# C-08_SODIMM_-.net
KiCad netlist of a schematic drawn in Altium Designer
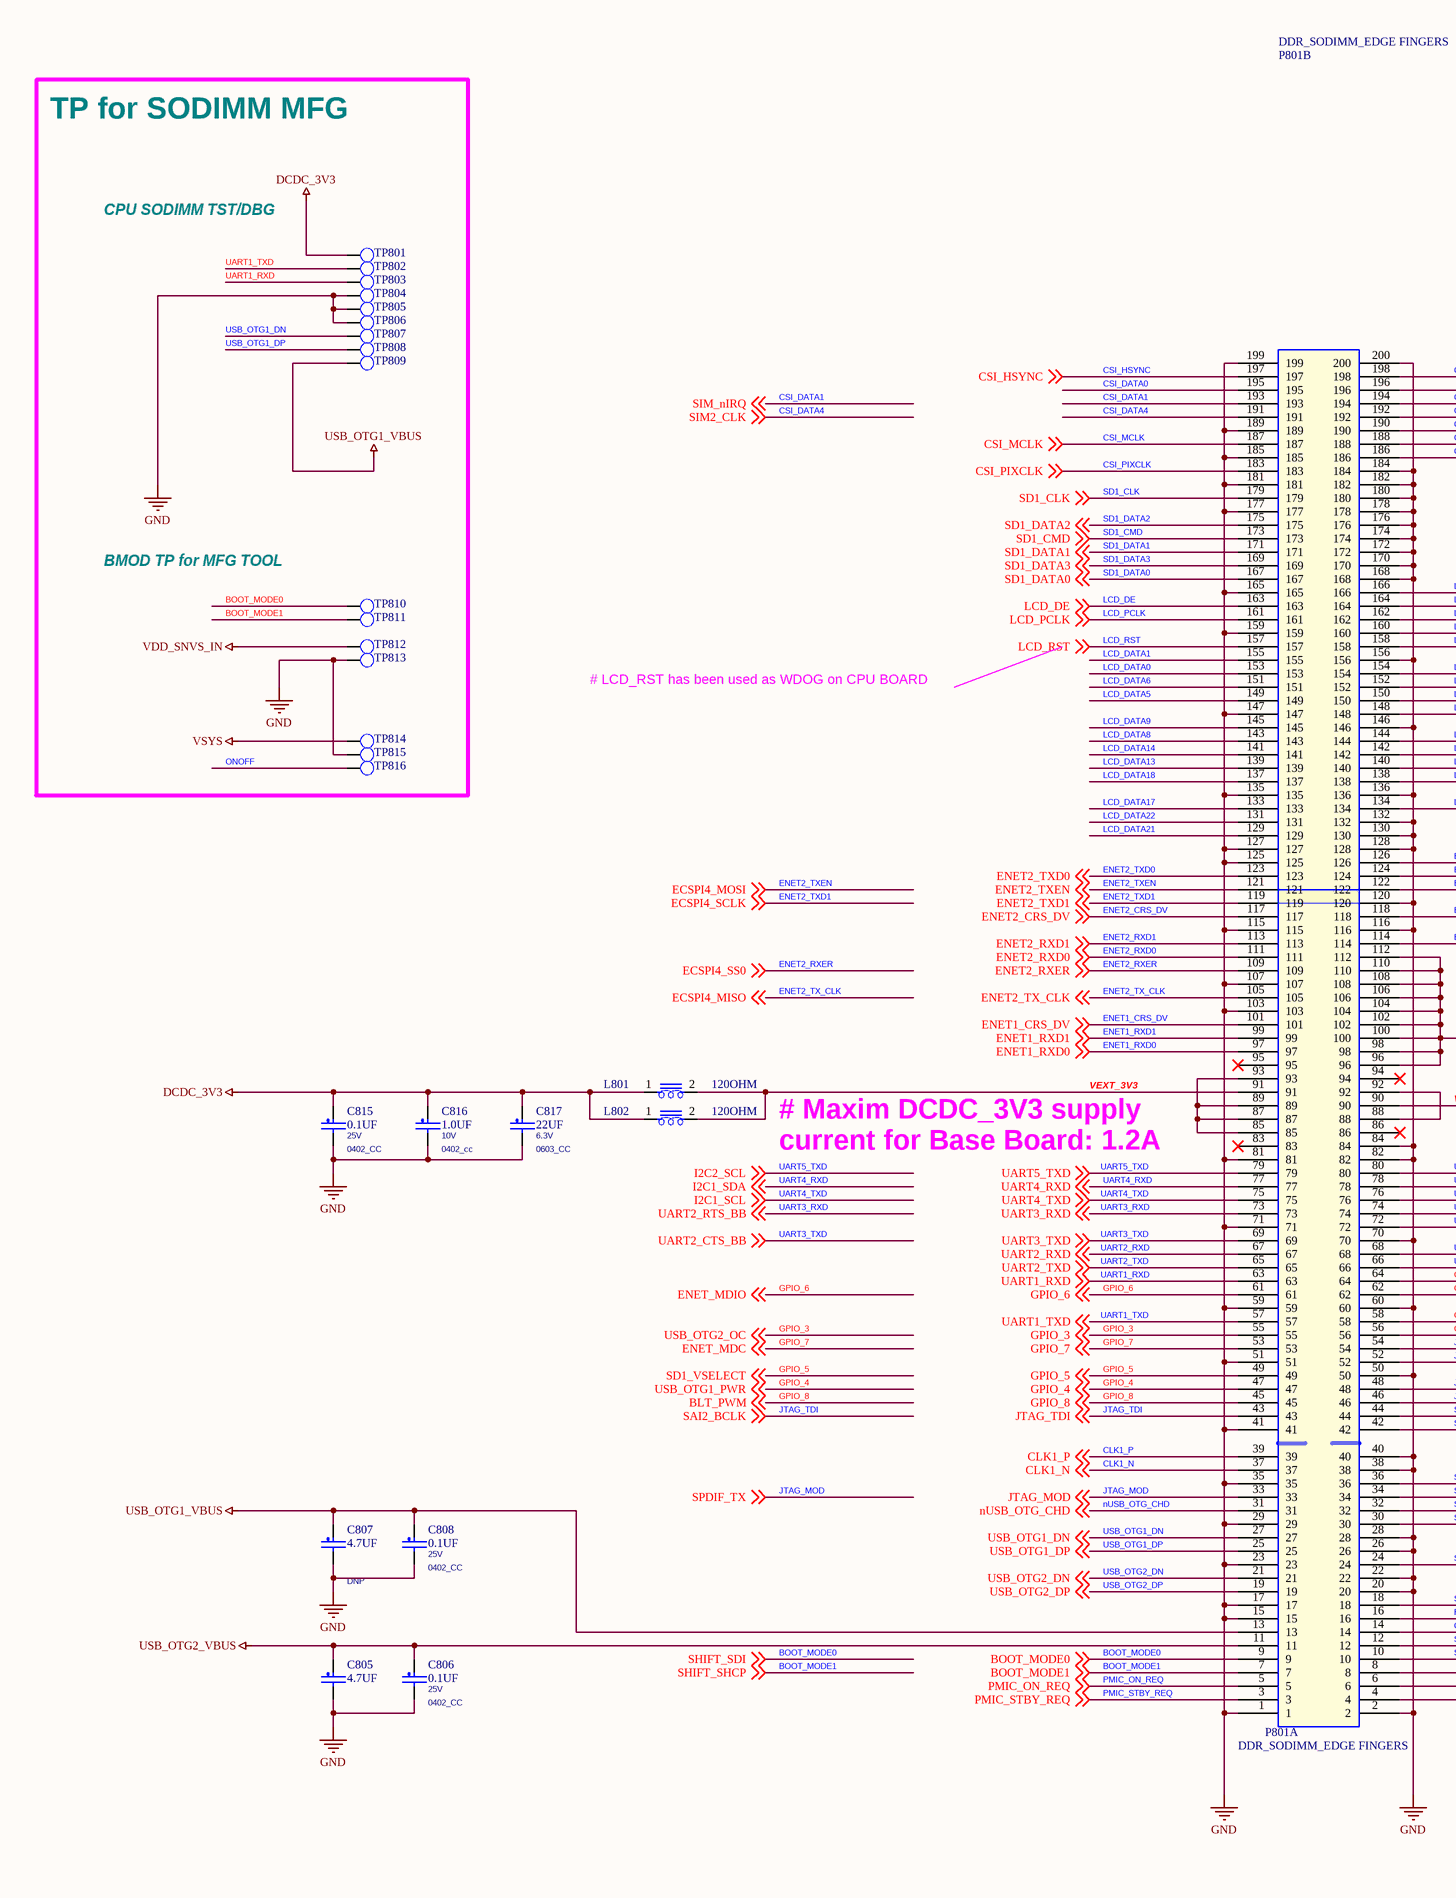
[diagram p0: C-08 SODIMM - 副本.SchDoc, left]
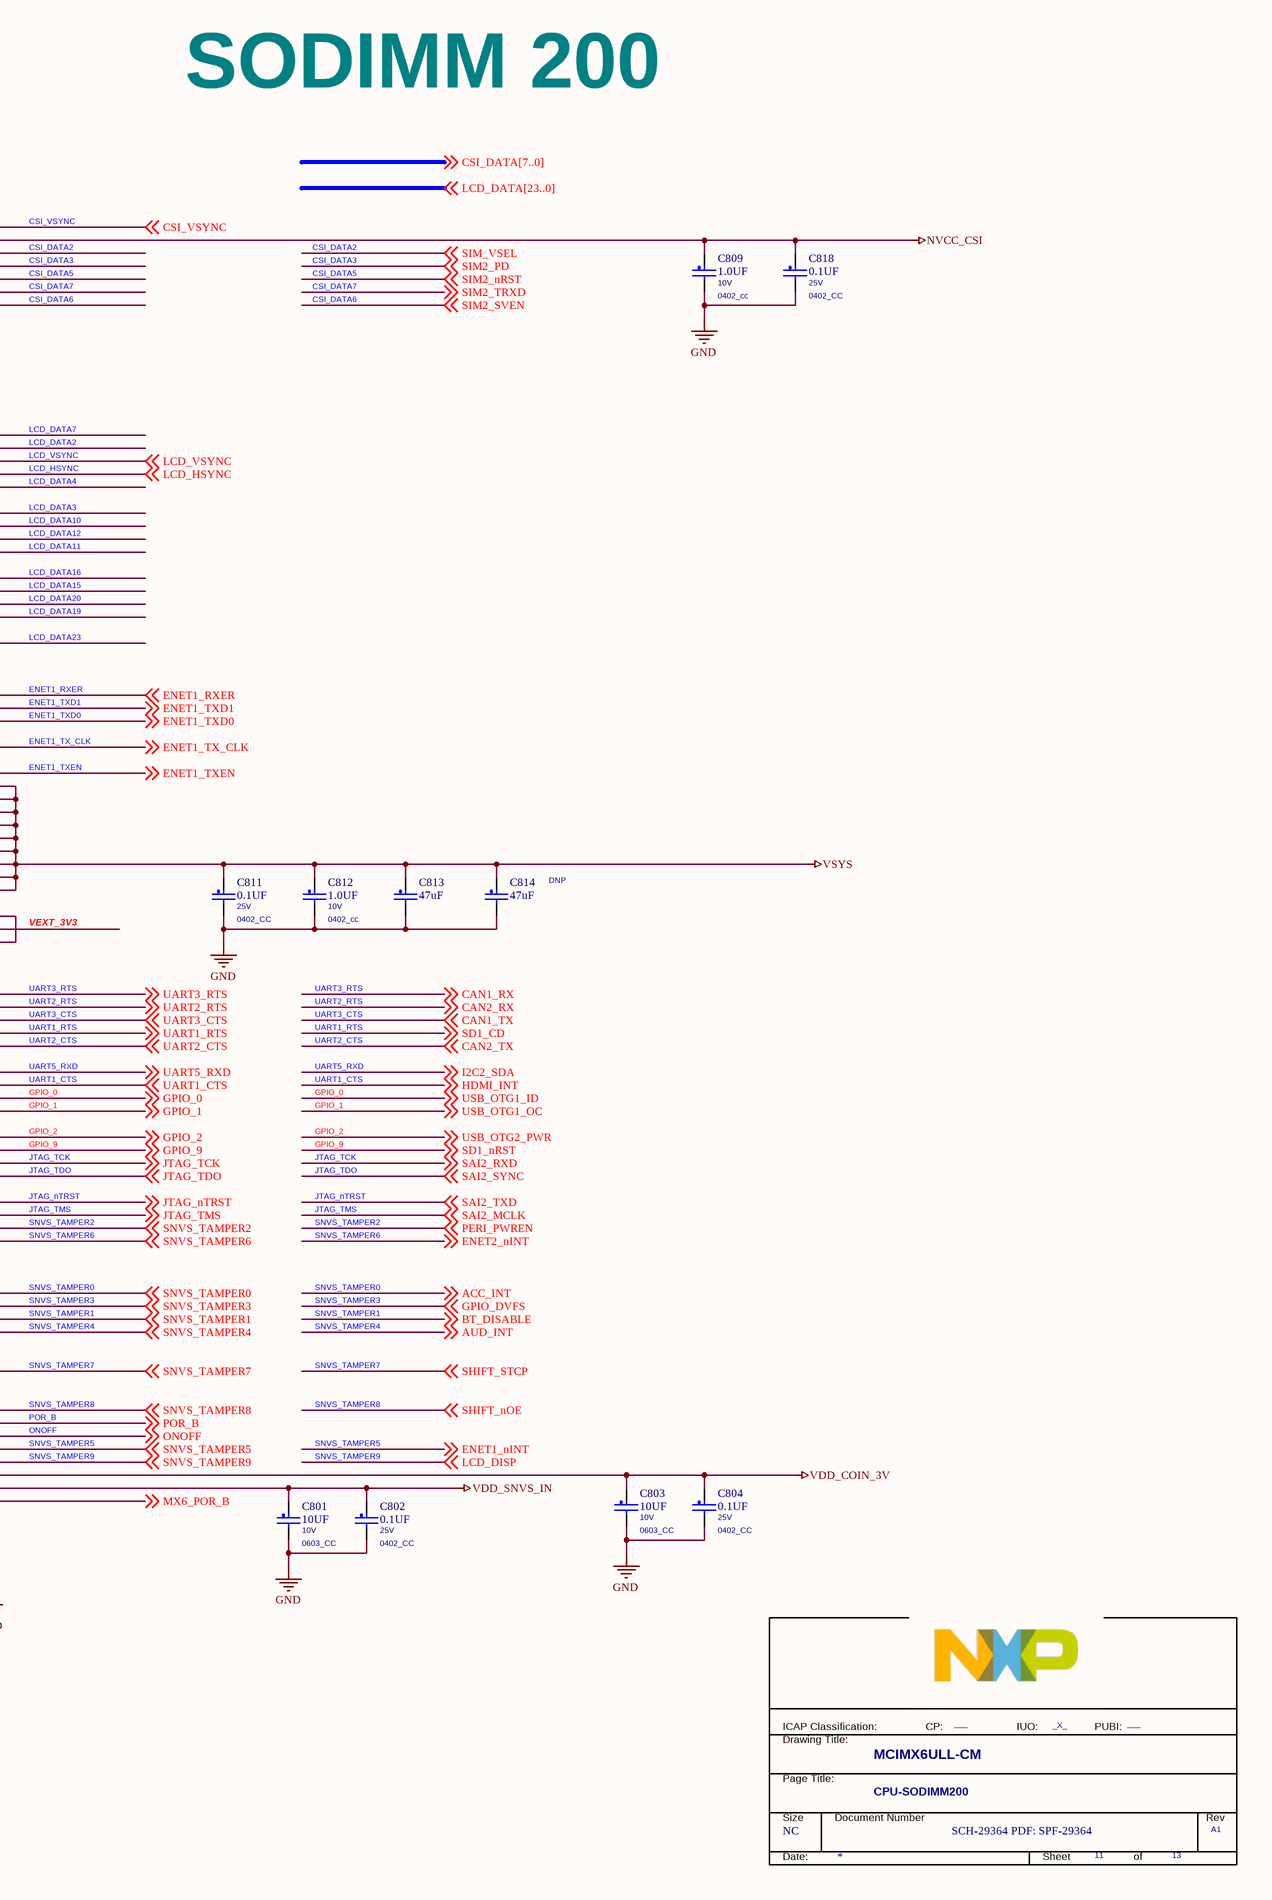
[diagram p1: C-08 SODIMM - 副本.SchDoc, right]

(export (version "E")
  (design (tool "Eeschema 10.0.6"))
  (components
    (comp (ref "*")
      (value "TitleBlock_FS")
      (fields
        (field (name "PAGETITLE") "CPU-SODIMM200")
        (field (name "PAGE COUNT") "13")
        (field (name "PAGE NUMBER") "11")
        (field (name "PAGE SIZE") "NC")
        (field (name "TITLE") "MCIMX6ULL-CM")
        (field (name "REVCODE") "A1")
        (field (name "DOC") "SCH-29364 PDF: SPF-29364")
        (field (name "FCP") "___")
        (field (name "PUBI") "___")
        (field (name "FIUO") "_X_")
      )
      (libsource (lib "*") (part "TitleBlock_FS"))
    )
    (comp (ref "C801")
      (value "10UF")
      (footprint "0603_CC")
      (description "CAP CER 10UF 10V 20% X5R 0603")
      (fields (field (name "VOLTAGE") "10V") (field (name "PCB FOOTPRINT") "0603_CC"))
      (libsource (lib "*") (part "CAP_NP"))
    )
    (comp (ref "C802")
      (value "0.1UF")
      (footprint "0402_CC")
      (description "CAP CER 0.1UF 25V 10% X5R 0402")
      (fields
        (field (name "VOLTAGE") "25V")
        (field (name "TOLERANCE") "10%")
        (field (name "PCB FOOTPRINT") "0402_CC")
      )
      (libsource (lib "*") (part "CAP_NP"))
    )
    (comp (ref "C803")
      (value "10UF")
      (footprint "0603_CC")
      (description "CAP CER 10UF 10V 20% X5R 0603")
      (fields (field (name "VOLTAGE") "10V") (field (name "PCB FOOTPRINT") "0603_CC"))
      (libsource (lib "*") (part "CAP_NP"))
    )
    (comp (ref "C804")
      (value "0.1UF")
      (footprint "0402_CC")
      (description "CAP CER 0.1UF 25V 10% X5R 0402")
      (fields
        (field (name "VOLTAGE") "25V")
        (field (name "TOLERANCE") "10%")
        (field (name "PCB FOOTPRINT") "0402_CC")
      )
      (libsource (lib "*") (part "CAP_NP"))
    )
    (comp (ref "C805")
      (value "4.7UF")
      (footprint "0603_CC")
      (description "CAP CER 4.7uF 16V 10% X5R 0603")
      (fields (field (name "VOLTAGE") "16V") (field (name "TOLERANCE") "10%"))
      (libsource (lib "*") (part "CAP_NP"))
    )
    (comp (ref "C806")
      (value "0.1UF")
      (footprint "0402_CC")
      (description "CAP CER 0.1UF 25V 10% X5R 0402")
      (fields
        (field (name "VOLTAGE") "25V")
        (field (name "TOLERANCE") "10%")
        (field (name "PCB FOOTPRINT") "0402_CC")
      )
      (libsource (lib "*") (part "CAP_NP"))
    )
    (comp (ref "C807")
      (value "4.7UF")
      (footprint "0603_CC")
      (description "CAP CER 4.7uF 16V 10% X5R 0603")
      (fields (field (name "ASSY_OPT") "DNP") (field (name "TOLERANCE") "10%") (field (name "VOLTAGE") "16V"))
      (libsource (lib "*") (part "CAP_NP"))
    )
    (comp (ref "C808")
      (value "0.1UF")
      (footprint "0402_CC")
      (description "CAP CER 0.1UF 25V 10% X5R 0402")
      (fields
        (field (name "VOLTAGE") "25V")
        (field (name "TOLERANCE") "10%")
        (field (name "PCB FOOTPRINT") "0402_CC")
      )
      (libsource (lib "*") (part "CAP_NP"))
    )
    (comp (ref "C809")
      (value "1.0UF")
      (footprint "0402_cc")
      (description "CAP CER 1.0UF 10V 10% X5R 0402")
      (fields (field (name "VOLTAGE") "10V") (field (name "PCB FOOTPRINT") "0402_cc"))
      (libsource (lib "*") (part "CAP_NP"))
    )
    (comp (ref "C811")
      (value "0.1UF")
      (footprint "0402_CC")
      (description "CAP CER 0.1UF 25V 10% X5R 0402")
      (fields
        (field (name "TOLERANCE") "10%")
        (field (name "VOLTAGE") "25V")
        (field (name "PCB FOOTPRINT") "0402_CC")
      )
      (libsource (lib "*") (part "CAP_NP"))
    )
    (comp (ref "C812")
      (value "1.0UF")
      (footprint "0402_cc")
      (description "CAP CER 1.0UF 10V 10% X5R 0402")
      (fields (field (name "VOLTAGE") "10V") (field (name "PCB FOOTPRINT") "0402_cc"))
      (libsource (lib "*") (part "CAP_NP"))
    )
    (comp (ref "C813")
      (value "47uF")
      (footprint "CC0805_OV")
      (description "CAP CER 47uF 10V 20% X5R 0805")
      (fields (field (name "TOLERANCE") "20%") (field (name "VOLTAGE") "10V"))
      (libsource (lib "*") (part "CAP_NP"))
    )
    (comp (ref "C814")
      (value "47uF")
      (footprint "CC0805_OV")
      (description "CAP CER 47uF 10V 20% X5R 0805")
      (fields (field (name "ASSY_OPT") "DNP") (field (name "TOLERANCE") "20%") (field (name "VOLTAGE") "10V"))
      (libsource (lib "*") (part "CAP_NP"))
    )
    (comp (ref "C815")
      (value "0.1UF")
      (footprint "0402_CC")
      (description "CAP CER 0.1UF 25V 10% X5R 0402")
      (fields
        (field (name "TOLERANCE") "10%")
        (field (name "VOLTAGE") "25V")
        (field (name "PCB FOOTPRINT") "0402_CC")
      )
      (libsource (lib "*") (part "CAP_NP"))
    )
    (comp (ref "C816")
      (value "1.0UF")
      (footprint "0402_cc")
      (description "CAP CER 1.0UF 10V 10% X5R 0402")
      (fields (field (name "VOLTAGE") "10V") (field (name "PCB FOOTPRINT") "0402_cc"))
      (libsource (lib "*") (part "CAP_NP"))
    )
    (comp (ref "C817")
      (value "22UF")
      (footprint "0603_CC")
      (description "CAP CER 22UF 6.3V 20% X5R 0603")
      (fields
        (field (name "VOLTAGE RATING") "6.3V")
        (field (name "TOLERANCE") "20%")
        (field (name "VOLTAGE") "6.3V")
        (field (name "PCB FOOTPRINT") "0603_CC")
      )
      (libsource (lib "*") (part "CAP_NP"))
    )
    (comp (ref "C818")
      (value "0.1UF")
      (footprint "0402_CC")
      (description "CAP CER 0.1UF 25V 10% X5R 0402")
      (fields
        (field (name "TOLERANCE") "10%")
        (field (name "VOLTAGE") "25V")
        (field (name "PCB FOOTPRINT") "0402_CC")
      )
      (libsource (lib "*") (part "CAP_NP"))
    )
    (comp (ref "L801")
      (value "120OHM")
      (footprint "0603_CC")
      (description "IND FER BEAD 120OHM@100MHZ 2A 25% 0603")
      (fields (field (name "TOLERANCE") "25%"))
      (libsource (lib "*") (part "BEAD_0"))
    )
    (comp (ref "L802")
      (value "120OHM")
      (footprint "0603_CC")
      (description "IND FER BEAD 120OHM@100MHZ 2A 25% 0603")
      (fields (field (name "TOLERANCE") "25%"))
      (libsource (lib "*") (part "BEAD_0"))
    )
    (comp (ref "P801")
      (value "DDR_SODIMM_EDGE FINGERS")
      (footprint "SODIMM_67589")
      (description "200 PIN SODIMM EDGE FINGERS -- AU FOOTPRINT ONLY, NO PART TO ORDER")
      (libsource (lib "*") (part "CONN_EDGE_200P"))
    )
    (comp (ref "TP801")
      (value "TP_35MIL")
      (footprint "testpoint_35mil")
      (description "TEST POINT PAD .035 SMT, no part to order")
      (libsource (lib "*") (part "T POINT R"))
    )
    (comp (ref "TP802")
      (value "TP_35MIL")
      (footprint "testpoint_35mil")
      (description "TEST POINT PAD .035 SMT, no part to order")
      (libsource (lib "*") (part "T POINT R"))
    )
    (comp (ref "TP803")
      (value "TP_35MIL")
      (footprint "testpoint_35mil")
      (description "TEST POINT PAD .035 SMT, no part to order")
      (libsource (lib "*") (part "T POINT R"))
    )
    (comp (ref "TP804")
      (value "TP_35MIL")
      (footprint "testpoint_35mil")
      (description "TEST POINT PAD .035 SMT, no part to order")
      (libsource (lib "*") (part "T POINT R"))
    )
    (comp (ref "TP805")
      (value "TP_35MIL")
      (footprint "testpoint_35mil")
      (description "TEST POINT PAD .035 SMT, no part to order")
      (libsource (lib "*") (part "T POINT R"))
    )
    (comp (ref "TP806")
      (value "TP_35MIL")
      (footprint "testpoint_35mil")
      (description "TEST POINT PAD .035 SMT, no part to order")
      (libsource (lib "*") (part "T POINT R"))
    )
    (comp (ref "TP807")
      (value "TP_35MIL")
      (footprint "testpoint_35mil")
      (description "TEST POINT PAD .035 SMT, no part to order")
      (libsource (lib "*") (part "T POINT R"))
    )
    (comp (ref "TP808")
      (value "TP_35MIL")
      (footprint "testpoint_35mil")
      (description "TEST POINT PAD .035 SMT, no part to order")
      (libsource (lib "*") (part "T POINT R"))
    )
    (comp (ref "TP809")
      (value "TP_35MIL")
      (footprint "testpoint_35mil")
      (description "TEST POINT PAD .035 SMT, no part to order")
      (libsource (lib "*") (part "T POINT R"))
    )
    (comp (ref "TP810")
      (value "TP_35MIL")
      (footprint "testpoint_35mil")
      (description "TEST POINT PAD .035 SMT, no part to order")
      (libsource (lib "*") (part "T POINT R"))
    )
    (comp (ref "TP811")
      (value "TP_35MIL")
      (footprint "testpoint_35mil")
      (description "TEST POINT PAD .035 SMT, no part to order")
      (libsource (lib "*") (part "T POINT R"))
    )
    (comp (ref "TP812")
      (value "TP_35MIL")
      (footprint "testpoint_35mil")
      (description "TEST POINT PAD .035 SMT, no part to order")
      (libsource (lib "*") (part "T POINT R"))
    )
    (comp (ref "TP813")
      (value "TP_35MIL")
      (footprint "testpoint_35mil")
      (description "TEST POINT PAD .035 SMT, no part to order")
      (libsource (lib "*") (part "T POINT R"))
    )
    (comp (ref "TP814")
      (value "TP_35MIL")
      (footprint "testpoint_35mil")
      (description "TEST POINT PAD .035 SMT, no part to order")
      (libsource (lib "*") (part "T POINT R"))
    )
    (comp (ref "TP815")
      (value "TP_35MIL")
      (footprint "testpoint_35mil")
      (description "TEST POINT PAD .035 SMT, no part to order")
      (libsource (lib "*") (part "T POINT R"))
    )
    (comp (ref "TP816")
      (value "TP_35MIL")
      (footprint "testpoint_35mil")
      (description "TEST POINT PAD .035 SMT, no part to order")
      (libsource (lib "*") (part "T POINT R"))
    )
  )
  (nets
    (net (code "1") (name "/VEXT_3V3") (class "Default")
      (node (ref "L801") (pin "2") (pinfunction "2_2") (pintype "passive"))
      (node (ref "L802") (pin "2") (pinfunction "2_2") (pintype "passive"))
      (node (ref "P801") (pin "90") (pinfunction "90_90") (pintype "passive"))
      (node (ref "P801") (pin "91") (pinfunction "91_91") (pintype "passive"))
    )
    (net (code "2") (name "ACC_INT") (class "Default")
      (node (ref "P801") (pin "36") (pinfunction "36_36") (pintype "passive"))
    )
    (net (code "3") (name "AUD_INT") (class "Default")
      (node (ref "P801") (pin "30") (pinfunction "30_30") (pintype "passive"))
    )
    (net (code "4") (name "BLT_PWM") (class "Default")
      (node (ref "P801") (pin "45") (pinfunction "45_45") (pintype "passive"))
    )
    (net (code "5") (name "BOOT_MODE0") (class "Default")
      (node (ref "P801") (pin "9") (pinfunction "9_9") (pintype "passive"))
      (node (ref "TP810") (pin "1") (pinfunction "TP_1") (pintype "passive"))
    )
    (net (code "6") (name "BOOT_MODE1") (class "Default")
      (node (ref "P801") (pin "7") (pinfunction "7_7") (pintype "passive"))
      (node (ref "TP811") (pin "1") (pinfunction "TP_1") (pintype "passive"))
    )
    (net (code "7") (name "BT_DISABLE") (class "Default")
      (node (ref "P801") (pin "32") (pinfunction "32_32") (pintype "passive"))
    )
    (net (code "8") (name "CAN1_RX") (class "Default")
      (node (ref "P801") (pin "80") (pinfunction "80_80") (pintype "passive"))
    )
    (net (code "9") (name "CAN1_TX") (class "Default")
      (node (ref "P801") (pin "76") (pinfunction "76_76") (pintype "passive"))
    )
    (net (code "10") (name "CAN2_RX") (class "Default")
      (node (ref "P801") (pin "78") (pinfunction "78_78") (pintype "passive"))
    )
    (net (code "11") (name "CAN2_TX") (class "Default")
      (node (ref "P801") (pin "72") (pinfunction "72_72") (pintype "passive"))
    )
    (net (code "12") (name "CLK1_N") (class "Default")
      (node (ref "P801") (pin "37") (pinfunction "37_37") (pintype "passive"))
    )
    (net (code "13") (name "CLK1_P") (class "Default")
      (node (ref "P801") (pin "39") (pinfunction "39_39") (pintype "passive"))
    )
    (net (code "14") (name "CSI_DATA0") (class "Default")
      (node (ref "P801") (pin "195") (pinfunction "195_195") (pintype "passive"))
    )
    (net (code "16") (name "CSI_HSYNC") (class "Default")
      (node (ref "P801") (pin "197") (pinfunction "197_197") (pintype "passive"))
    )
    (net (code "17") (name "CSI_MCLK") (class "Default")
      (node (ref "P801") (pin "187") (pinfunction "187_187") (pintype "passive"))
    )
    (net (code "18") (name "CSI_PIXCLK") (class "Default")
      (node (ref "P801") (pin "183") (pinfunction "183_183") (pintype "passive"))
    )
    (net (code "19") (name "CSI_VSYNC") (class "Default")
      (node (ref "P801") (pin "198") (pinfunction "198_198") (pintype "passive"))
    )
    (net (code "20") (name "DCDC_3V3") (class "Default")
      (node (ref "C815") (pin "1") (pinfunction "1_1") (pintype "passive"))
      (node (ref "C816") (pin "1") (pinfunction "1_1") (pintype "passive"))
      (node (ref "C817") (pin "1") (pinfunction "1_1") (pintype "passive"))
      (node (ref "L801") (pin "1") (pinfunction "1_1") (pintype "passive"))
      (node (ref "L802") (pin "1") (pinfunction "1_1") (pintype "passive"))
      (node (ref "TP801") (pin "1") (pinfunction "TP_1") (pintype "passive"))
    )
    (net (code "21") (name "ECSPI4_MISO") (class "Default")
      (node (ref "P801") (pin "105") (pinfunction "105_105") (pintype "passive"))
    )
    (net (code "22") (name "ECSPI4_MOSI") (class "Default")
      (node (ref "P801") (pin "121") (pinfunction "121_121") (pintype "passive"))
    )
    (net (code "23") (name "ECSPI4_SCLK") (class "Default")
      (node (ref "P801") (pin "119") (pinfunction "119_119") (pintype "passive"))
    )
    (net (code "24") (name "ECSPI4_SS0") (class "Default")
      (node (ref "P801") (pin "109") (pinfunction "109_109") (pintype "passive"))
    )
    (net (code "25") (name "ENET1_CRS_DV") (class "Default")
      (node (ref "P801") (pin "101") (pinfunction "101_101") (pintype "passive"))
    )
    (net (code "26") (name "ENET1_RXD0") (class "Default")
      (node (ref "P801") (pin "97") (pinfunction "97_97") (pintype "passive"))
    )
    (net (code "27") (name "ENET1_RXD1") (class "Default")
      (node (ref "P801") (pin "99") (pinfunction "99_99") (pintype "passive"))
    )
    (net (code "28") (name "ENET1_RXER") (class "Default")
      (node (ref "P801") (pin "126") (pinfunction "126_126") (pintype "passive"))
    )
    (net (code "29") (name "ENET1_TXD0") (class "Default")
      (node (ref "P801") (pin "122") (pinfunction "122_122") (pintype "passive"))
    )
    (net (code "30") (name "ENET1_TXD1") (class "Default")
      (node (ref "P801") (pin "124") (pinfunction "124_124") (pintype "passive"))
    )
    (net (code "31") (name "ENET1_TXEN") (class "Default")
      (node (ref "P801") (pin "114") (pinfunction "114_114") (pintype "passive"))
    )
    (net (code "32") (name "ENET1_TX_CLK") (class "Default")
      (node (ref "P801") (pin "118") (pinfunction "118_118") (pintype "passive"))
    )
    (net (code "33") (name "ENET1_nINT") (class "Default")
      (node (ref "P801") (pin "12") (pinfunction "12_12") (pintype "passive"))
    )
    (net (code "34") (name "ENET2_CRS_DV") (class "Default")
      (node (ref "P801") (pin "117") (pinfunction "117_117") (pintype "passive"))
    )
    (net (code "35") (name "ENET2_RXD0") (class "Default")
      (node (ref "P801") (pin "111") (pinfunction "111_111") (pintype "passive"))
    )
    (net (code "36") (name "ENET2_RXD1") (class "Default")
      (node (ref "P801") (pin "113") (pinfunction "113_113") (pintype "passive"))
    )
    (net (code "37") (name "ENET2_TXD0") (class "Default")
      (node (ref "P801") (pin "123") (pinfunction "123_123") (pintype "passive"))
    )
    (net (code "38") (name "ENET2_nINT") (class "Default")
      (node (ref "P801") (pin "42") (pinfunction "42_42") (pintype "passive"))
    )
    (net (code "39") (name "ENET_MDC") (class "Default")
      (node (ref "P801") (pin "53") (pinfunction "53_53") (pintype "passive"))
    )
    (net (code "40") (name "ENET_MDIO") (class "Default")
      (node (ref "P801") (pin "61") (pinfunction "61_61") (pintype "passive"))
    )
    (net (code "41") (name "GND") (class "Default")
      (node (ref "C801") (pin "2") (pinfunction "2_2") (pintype "passive"))
      (node (ref "C802") (pin "2") (pinfunction "2_2") (pintype "passive"))
      (node (ref "C803") (pin "2") (pinfunction "2_2") (pintype "passive"))
      (node (ref "C804") (pin "2") (pinfunction "2_2") (pintype "passive"))
      (node (ref "C805") (pin "2") (pinfunction "2_2") (pintype "passive"))
      (node (ref "C806") (pin "2") (pinfunction "2_2") (pintype "passive"))
      (node (ref "C807") (pin "2") (pinfunction "2_2") (pintype "passive"))
      (node (ref "C808") (pin "2") (pinfunction "2_2") (pintype "passive"))
      (node (ref "C809") (pin "2") (pinfunction "2_2") (pintype "passive"))
      (node (ref "C811") (pin "2") (pinfunction "2_2") (pintype "passive"))
      (node (ref "C812") (pin "2") (pinfunction "2_2") (pintype "passive"))
      (node (ref "C813") (pin "2") (pinfunction "2_2") (pintype "passive"))
      (node (ref "C814") (pin "2") (pinfunction "2_2") (pintype "passive"))
      (node (ref "C815") (pin "2") (pinfunction "2_2") (pintype "passive"))
      (node (ref "C816") (pin "2") (pinfunction "2_2") (pintype "passive"))
      (node (ref "C817") (pin "2") (pinfunction "2_2") (pintype "passive"))
      (node (ref "C818") (pin "2") (pinfunction "2_2") (pintype "passive"))
      (node (ref "P801") (pin "1") (pinfunction "1_1") (pintype "passive"))
      (node (ref "P801") (pin "103") (pinfunction "103_103") (pintype "passive"))
      (node (ref "P801") (pin "107") (pinfunction "107_107") (pintype "passive"))
      (node (ref "P801") (pin "115") (pinfunction "115_115") (pintype "passive"))
      (node (ref "P801") (pin "116") (pinfunction "116_116") (pintype "passive"))
      (node (ref "P801") (pin "120") (pinfunction "120_120") (pintype "passive"))
      (node (ref "P801") (pin "125") (pinfunction "125_125") (pintype "passive"))
      (node (ref "P801") (pin "127") (pinfunction "127_127") (pintype "passive"))
      (node (ref "P801") (pin "128") (pinfunction "128_128") (pintype "passive"))
      (node (ref "P801") (pin "130") (pinfunction "130_130") (pintype "passive"))
      (node (ref "P801") (pin "132") (pinfunction "132_132") (pintype "passive"))
      (node (ref "P801") (pin "135") (pinfunction "135_135") (pintype "passive"))
      (node (ref "P801") (pin "136") (pinfunction "136_136") (pintype "passive"))
      (node (ref "P801") (pin "146") (pinfunction "146_146") (pintype "passive"))
      (node (ref "P801") (pin "147") (pinfunction "147_147") (pintype "passive"))
      (node (ref "P801") (pin "15") (pinfunction "15_15") (pintype "passive"))
      (node (ref "P801") (pin "156") (pinfunction "156_156") (pintype "passive"))
      (node (ref "P801") (pin "159") (pinfunction "159_159") (pintype "passive"))
      (node (ref "P801") (pin "165") (pinfunction "165_165") (pintype "passive"))
      (node (ref "P801") (pin "168") (pinfunction "168_168") (pintype "passive"))
      (node (ref "P801") (pin "17") (pinfunction "17_17") (pintype "passive"))
      (node (ref "P801") (pin "170") (pinfunction "170_170") (pintype "passive"))
      (node (ref "P801") (pin "172") (pinfunction "172_172") (pintype "passive"))
      (node (ref "P801") (pin "174") (pinfunction "174_174") (pintype "passive"))
      (node (ref "P801") (pin "176") (pinfunction "176_176") (pintype "passive"))
      (node (ref "P801") (pin "177") (pinfunction "177_177") (pintype "passive"))
      (node (ref "P801") (pin "178") (pinfunction "178_178") (pintype "passive"))
      (node (ref "P801") (pin "180") (pinfunction "180_180") (pintype "passive"))
      (node (ref "P801") (pin "181") (pinfunction "181_181") (pintype "passive"))
      (node (ref "P801") (pin "182") (pinfunction "182_182") (pintype "passive"))
      (node (ref "P801") (pin "184") (pinfunction "184_184") (pintype "passive"))
      (node (ref "P801") (pin "185") (pinfunction "185_185") (pintype "passive"))
      (node (ref "P801") (pin "189") (pinfunction "189_189") (pintype "passive"))
      (node (ref "P801") (pin "199") (pinfunction "199_199") (pintype "passive"))
      (node (ref "P801") (pin "2") (pinfunction "2_2") (pintype "passive"))
      (node (ref "P801") (pin "20") (pinfunction "20_20") (pintype "passive"))
      (node (ref "P801") (pin "200") (pinfunction "200_200") (pintype "passive"))
      (node (ref "P801") (pin "22") (pinfunction "22_22") (pintype "passive"))
      (node (ref "P801") (pin "23") (pinfunction "23_23") (pintype "passive"))
      (node (ref "P801") (pin "26") (pinfunction "26_26") (pintype "passive"))
      (node (ref "P801") (pin "28") (pinfunction "28_28") (pintype "passive"))
      (node (ref "P801") (pin "29") (pinfunction "29_29") (pintype "passive"))
      (node (ref "P801") (pin "35") (pinfunction "35_35") (pintype "passive"))
      (node (ref "P801") (pin "38") (pinfunction "38_38") (pintype "passive"))
      (node (ref "P801") (pin "40") (pinfunction "40_40") (pintype "passive"))
      (node (ref "P801") (pin "41") (pinfunction "41_41") (pintype "passive"))
      (node (ref "P801") (pin "50") (pinfunction "50_50") (pintype "passive"))
      (node (ref "P801") (pin "51") (pinfunction "51_51") (pintype "passive"))
      (node (ref "P801") (pin "59") (pinfunction "59_59") (pintype "passive"))
      (node (ref "P801") (pin "60") (pinfunction "60_60") (pintype "passive"))
      (node (ref "P801") (pin "70") (pinfunction "70_70") (pintype "passive"))
      (node (ref "P801") (pin "71") (pinfunction "71_71") (pintype "passive"))
      (node (ref "P801") (pin "81") (pinfunction "81_81") (pintype "passive"))
      (node (ref "P801") (pin "82") (pinfunction "82_82") (pintype "passive"))
      (node (ref "P801") (pin "84") (pinfunction "84_84") (pintype "passive"))
      (node (ref "TP804") (pin "1") (pinfunction "TP_1") (pintype "passive"))
      (node (ref "TP805") (pin "1") (pinfunction "TP_1") (pintype "passive"))
      (node (ref "TP806") (pin "1") (pinfunction "TP_1") (pintype "passive"))
      (node (ref "TP813") (pin "1") (pinfunction "TP_1") (pintype "passive"))
      (node (ref "TP815") (pin "1") (pinfunction "TP_1") (pintype "passive"))
    )
    (net (code "42") (name "GPIO_0") (class "Default")
      (node (ref "P801") (pin "64") (pinfunction "64_64") (pintype "passive"))
    )
    (net (code "43") (name "GPIO_1") (class "Default")
      (node (ref "P801") (pin "62") (pinfunction "62_62") (pintype "passive"))
    )
    (net (code "44") (name "GPIO_2") (class "Default")
      (node (ref "P801") (pin "58") (pinfunction "58_58") (pintype "passive"))
    )
    (net (code "45") (name "GPIO_3") (class "Default")
      (node (ref "P801") (pin "55") (pinfunction "55_55") (pintype "passive"))
    )
    (net (code "46") (name "GPIO_4") (class "Default")
      (node (ref "P801") (pin "47") (pinfunction "47_47") (pintype "passive"))
    )
    (net (code "47") (name "GPIO_5") (class "Default")
      (node (ref "P801") (pin "49") (pinfunction "49_49") (pintype "passive"))
    )
    (net (code "48") (name "GPIO_9") (class "Default")
      (node (ref "P801") (pin "56") (pinfunction "56_56") (pintype "passive"))
    )
    (net (code "49") (name "GPIO_DVFS") (class "Default")
      (node (ref "P801") (pin "34") (pinfunction "34_34") (pintype "passive"))
    )
    (net (code "50") (name "HDMI_INT") (class "Default")
      (node (ref "P801") (pin "66") (pinfunction "66_66") (pintype "passive"))
    )
    (net (code "51") (name "I2C1_SCL") (class "Default")
      (node (ref "P801") (pin "75") (pinfunction "75_75") (pintype "passive"))
    )
    (net (code "52") (name "I2C1_SDA") (class "Default")
      (node (ref "P801") (pin "77") (pinfunction "77_77") (pintype "passive"))
    )
    (net (code "53") (name "I2C2_SCL") (class "Default")
      (node (ref "P801") (pin "79") (pinfunction "79_79") (pintype "passive"))
    )
    (net (code "54") (name "I2C2_SDA") (class "Default")
      (node (ref "P801") (pin "68") (pinfunction "68_68") (pintype "passive"))
    )
    (net (code "55") (name "JTAG_MOD") (class "Default")
      (node (ref "P801") (pin "33") (pinfunction "33_33") (pintype "passive"))
    )
    (net (code "56") (name "JTAG_TCK") (class "Default")
      (node (ref "P801") (pin "54") (pinfunction "54_54") (pintype "passive"))
    )
    (net (code "57") (name "JTAG_TDI") (class "Default")
      (node (ref "P801") (pin "43") (pinfunction "43_43") (pintype "passive"))
    )
    (net (code "58") (name "JTAG_TDO") (class "Default")
      (node (ref "P801") (pin "52") (pinfunction "52_52") (pintype "passive"))
    )
    (net (code "59") (name "JTAG_TMS") (class "Default")
      (node (ref "P801") (pin "46") (pinfunction "46_46") (pintype "passive"))
    )
    (net (code "60") (name "JTAG_nTRST") (class "Default")
      (node (ref "P801") (pin "48") (pinfunction "48_48") (pintype "passive"))
    )
    (net (code "61") (name "LCD_DATA0") (class "Default")
      (node (ref "P801") (pin "153") (pinfunction "153_153") (pintype "passive"))
    )
    (net (code "62") (name "LCD_DATA1") (class "Default")
      (node (ref "P801") (pin "155") (pinfunction "155_155") (pintype "passive"))
    )
    (net (code "63") (name "LCD_DATA2") (class "Default")
      (node (ref "P801") (pin "164") (pinfunction "164_164") (pintype "passive"))
    )
    (net (code "64") (name "LCD_DATA3") (class "Default")
      (node (ref "P801") (pin "154") (pinfunction "154_154") (pintype "passive"))
    )
    (net (code "65") (name "LCD_DATA4") (class "Default")
      (node (ref "P801") (pin "158") (pinfunction "158_158") (pintype "passive"))
    )
    (net (code "66") (name "LCD_DATA5") (class "Default")
      (node (ref "P801") (pin "149") (pinfunction "149_149") (pintype "passive"))
    )
    (net (code "67") (name "LCD_DATA6") (class "Default")
      (node (ref "P801") (pin "151") (pinfunction "151_151") (pintype "passive"))
    )
    (net (code "68") (name "LCD_DATA7") (class "Default")
      (node (ref "P801") (pin "166") (pinfunction "166_166") (pintype "passive"))
    )
    (net (code "69") (name "LCD_DATA8") (class "Default")
      (node (ref "P801") (pin "143") (pinfunction "143_143") (pintype "passive"))
    )
    (net (code "70") (name "LCD_DATA9") (class "Default")
      (node (ref "P801") (pin "145") (pinfunction "145_145") (pintype "passive"))
    )
    (net (code "71") (name "LCD_DATA10") (class "Default")
      (node (ref "P801") (pin "152") (pinfunction "152_152") (pintype "passive"))
    )
    (net (code "72") (name "LCD_DATA11") (class "Default")
      (node (ref "P801") (pin "148") (pinfunction "148_148") (pintype "passive"))
    )
    (net (code "73") (name "LCD_DATA12") (class "Default")
      (node (ref "P801") (pin "150") (pinfunction "150_150") (pintype "passive"))
    )
    (net (code "74") (name "LCD_DATA13") (class "Default")
      (node (ref "P801") (pin "139") (pinfunction "139_139") (pintype "passive"))
    )
    (net (code "75") (name "LCD_DATA14") (class "Default")
      (node (ref "P801") (pin "141") (pinfunction "141_141") (pintype "passive"))
    )
    (net (code "76") (name "LCD_DATA15") (class "Default")
      (node (ref "P801") (pin "142") (pinfunction "142_142") (pintype "passive"))
    )
    (net (code "77") (name "LCD_DATA16") (class "Default")
      (node (ref "P801") (pin "144") (pinfunction "144_144") (pintype "passive"))
    )
    (net (code "78") (name "LCD_DATA17") (class "Default")
      (node (ref "P801") (pin "133") (pinfunction "133_133") (pintype "passive"))
    )
    (net (code "79") (name "LCD_DATA18") (class "Default")
      (node (ref "P801") (pin "137") (pinfunction "137_137") (pintype "passive"))
    )
    (net (code "80") (name "LCD_DATA19") (class "Default")
      (node (ref "P801") (pin "138") (pinfunction "138_138") (pintype "passive"))
    )
    (net (code "81") (name "LCD_DATA20") (class "Default")
      (node (ref "P801") (pin "140") (pinfunction "140_140") (pintype "passive"))
    )
    (net (code "82") (name "LCD_DATA21") (class "Default")
      (node (ref "P801") (pin "129") (pinfunction "129_129") (pintype "passive"))
    )
    (net (code "83") (name "LCD_DATA22") (class "Default")
      (node (ref "P801") (pin "131") (pinfunction "131_131") (pintype "passive"))
    )
    (net (code "84") (name "LCD_DATA23") (class "Default")
      (node (ref "P801") (pin "134") (pinfunction "134_134") (pintype "passive"))
    )
    (net (code "86") (name "LCD_DE") (class "Default")
      (node (ref "P801") (pin "163") (pinfunction "163_163") (pintype "passive"))
    )
    (net (code "87") (name "LCD_DISP") (class "Default")
      (node (ref "P801") (pin "10") (pinfunction "10_10") (pintype "passive"))
    )
    (net (code "88") (name "LCD_HSYNC") (class "Default")
      (node (ref "P801") (pin "160") (pinfunction "160_160") (pintype "passive"))
    )
    (net (code "89") (name "LCD_PCLK") (class "Default")
      (node (ref "P801") (pin "161") (pinfunction "161_161") (pintype "passive"))
    )
    (net (code "90") (name "LCD_RST") (class "Default")
      (node (ref "P801") (pin "157") (pinfunction "157_157") (pintype "passive"))
    )
    (net (code "91") (name "LCD_VSYNC") (class "Default")
      (node (ref "P801") (pin "162") (pinfunction "162_162") (pintype "passive"))
    )
    (net (code "92") (name "MX6_POR_B") (class "Default")
      (node (ref "P801") (pin "4") (pinfunction "4_4") (pintype "passive"))
    )
    (net (code "93") (name "NVCC_CSI") (class "Default")
      (node (ref "C809") (pin "1") (pinfunction "1_1") (pintype "passive"))
      (node (ref "C818") (pin "1") (pinfunction "1_1") (pintype "passive"))
      (node (ref "P801") (pin "196") (pinfunction "196_196") (pintype "passive"))
    )
    (net (code "94") (name "Net-(P801-Pad85)") (class "Default")
      (node (ref "P801") (pin "85") (pinfunction "85_85") (pintype "passive"))
      (node (ref "P801") (pin "87") (pinfunction "87_87") (pintype "passive"))
      (node (ref "P801") (pin "89") (pinfunction "89_89") (pintype "passive"))
      (node (ref "P801") (pin "93") (pinfunction "93_93") (pintype "passive"))
    )
    (net (code "95") (name "Net-(P801-Pad88)") (class "Default")
      (node (ref "P801") (pin "88") (pinfunction "88_88") (pintype "passive"))
      (node (ref "P801") (pin "92") (pinfunction "92_92") (pintype "passive"))
    )
    (net (code "96") (name "ONOFF") (class "Default")
      (node (ref "P801") (pin "14") (pinfunction "14_14") (pintype "passive"))
      (node (ref "TP816") (pin "1") (pinfunction "TP_1") (pintype "passive"))
    )
    (net (code "97") (name "PERI_PWREN") (class "Default")
      (node (ref "P801") (pin "44") (pinfunction "44_44") (pintype "passive"))
    )
    (net (code "98") (name "PMIC_ON_REQ") (class "Default")
      (node (ref "P801") (pin "5") (pinfunction "5_5") (pintype "passive"))
    )
    (net (code "99") (name "PMIC_STBY_REQ") (class "Default")
      (node (ref "P801") (pin "3") (pinfunction "3_3") (pintype "passive"))
    )
    (net (code "100") (name "POR_B") (class "Default")
      (node (ref "P801") (pin "16") (pinfunction "16_16") (pintype "passive"))
    )
    (net (code "101") (name "SD1_CD") (class "Default")
      (node (ref "P801") (pin "74") (pinfunction "74_74") (pintype "passive"))
    )
    (net (code "102") (name "SD1_CLK") (class "Default")
      (node (ref "P801") (pin "179") (pinfunction "179_179") (pintype "passive"))
    )
    (net (code "103") (name "SD1_CMD") (class "Default")
      (node (ref "P801") (pin "173") (pinfunction "173_173") (pintype "passive"))
    )
    (net (code "104") (name "SD1_DATA0") (class "Default")
      (node (ref "P801") (pin "167") (pinfunction "167_167") (pintype "passive"))
    )
    (net (code "105") (name "SD1_DATA1") (class "Default")
      (node (ref "P801") (pin "171") (pinfunction "171_171") (pintype "passive"))
    )
    (net (code "106") (name "SD1_DATA2") (class "Default")
      (node (ref "P801") (pin "175") (pinfunction "175_175") (pintype "passive"))
    )
    (net (code "107") (name "SD1_DATA3") (class "Default")
      (node (ref "P801") (pin "169") (pinfunction "169_169") (pintype "passive"))
    )
    (net (code "108") (name "SHIFT_STCP") (class "Default")
      (node (ref "P801") (pin "24") (pinfunction "24_24") (pintype "passive"))
    )
    (net (code "109") (name "SHIFT_nOE") (class "Default")
      (node (ref "P801") (pin "18") (pinfunction "18_18") (pintype "passive"))
    )
    (net (code "110") (name "SIM2_CLK") (class "Default")
      (node (ref "P801") (pin "191") (pinfunction "191_191") (pintype "passive"))
    )
    (net (code "111") (name "SIM2_PD") (class "Default")
      (node (ref "P801") (pin "192") (pinfunction "192_192") (pintype "passive"))
    )
    (net (code "112") (name "SIM2_SVEN") (class "Default")
      (node (ref "P801") (pin "186") (pinfunction "186_186") (pintype "passive"))
    )
    (net (code "113") (name "SIM2_TRXD") (class "Default")
      (node (ref "P801") (pin "188") (pinfunction "188_188") (pintype "passive"))
    )
    (net (code "114") (name "SIM2_nRST") (class "Default")
      (node (ref "P801") (pin "190") (pinfunction "190_190") (pintype "passive"))
    )
    (net (code "115") (name "SIM_VSEL") (class "Default")
      (node (ref "P801") (pin "194") (pinfunction "194_194") (pintype "passive"))
    )
    (net (code "116") (name "SIM_nIRQ") (class "Default")
      (node (ref "P801") (pin "193") (pinfunction "193_193") (pintype "passive"))
    )
    (net (code "117") (name "UART1_RXD") (class "Default")
      (node (ref "P801") (pin "63") (pinfunction "63_63") (pintype "passive"))
      (node (ref "TP803") (pin "1") (pinfunction "TP_1") (pintype "passive"))
    )
    (net (code "118") (name "UART1_TXD") (class "Default")
      (node (ref "P801") (pin "57") (pinfunction "57_57") (pintype "passive"))
      (node (ref "TP802") (pin "1") (pinfunction "TP_1") (pintype "passive"))
    )
    (net (code "119") (name "UART2_CTS_BB") (class "Default")
      (node (ref "P801") (pin "69") (pinfunction "69_69") (pintype "passive"))
    )
    (net (code "120") (name "UART2_RTS_BB") (class "Default")
      (node (ref "P801") (pin "73") (pinfunction "73_73") (pintype "passive"))
    )
    (net (code "121") (name "UART2_RXD") (class "Default")
      (node (ref "P801") (pin "67") (pinfunction "67_67") (pintype "passive"))
    )
    (net (code "122") (name "UART2_TXD") (class "Default")
      (node (ref "P801") (pin "65") (pinfunction "65_65") (pintype "passive"))
    )
    (net (code "123") (name "USB_OTG1_DN") (class "Default")
      (node (ref "P801") (pin "27") (pinfunction "27_27") (pintype "passive"))
      (node (ref "TP807") (pin "1") (pinfunction "TP_1") (pintype "passive"))
    )
    (net (code "124") (name "USB_OTG1_DP") (class "Default")
      (node (ref "P801") (pin "25") (pinfunction "25_25") (pintype "passive"))
      (node (ref "TP808") (pin "1") (pinfunction "TP_1") (pintype "passive"))
    )
    (net (code "125") (name "USB_OTG1_VBUS") (class "Default")
      (node (ref "C807") (pin "1") (pinfunction "1_1") (pintype "passive"))
      (node (ref "C808") (pin "1") (pinfunction "1_1") (pintype "passive"))
      (node (ref "P801") (pin "13") (pinfunction "13_13") (pintype "passive"))
      (node (ref "TP809") (pin "1") (pinfunction "TP_1") (pintype "passive"))
    )
    (net (code "126") (name "USB_OTG2_DN") (class "Default")
      (node (ref "P801") (pin "21") (pinfunction "21_21") (pintype "passive"))
    )
    (net (code "127") (name "USB_OTG2_DP") (class "Default")
      (node (ref "P801") (pin "19") (pinfunction "19_19") (pintype "passive"))
    )
    (net (code "128") (name "USB_OTG2_VBUS") (class "Default")
      (node (ref "C805") (pin "1") (pinfunction "1_1") (pintype "passive"))
      (node (ref "C806") (pin "1") (pinfunction "1_1") (pintype "passive"))
      (node (ref "P801") (pin "11") (pinfunction "11_11") (pintype "passive"))
    )
    (net (code "129") (name "VDD_COIN_3V") (class "Default")
      (node (ref "C803") (pin "1") (pinfunction "1_1") (pintype "passive"))
      (node (ref "C804") (pin "1") (pinfunction "1_1") (pintype "passive"))
      (node (ref "P801") (pin "8") (pinfunction "8_8") (pintype "passive"))
    )
    (net (code "130") (name "VDD_SNVS_IN") (class "Default")
      (node (ref "C801") (pin "1") (pinfunction "1_1") (pintype "passive"))
      (node (ref "C802") (pin "1") (pinfunction "1_1") (pintype "passive"))
      (node (ref "P801") (pin "6") (pinfunction "6_6") (pintype "passive"))
      (node (ref "TP812") (pin "1") (pinfunction "TP_1") (pintype "passive"))
    )
    (net (code "131") (name "VSYS") (class "Default")
      (node (ref "C811") (pin "1") (pinfunction "1_1") (pintype "passive"))
      (node (ref "C812") (pin "1") (pinfunction "1_1") (pintype "passive"))
      (node (ref "C813") (pin "1") (pinfunction "1_1") (pintype "passive"))
      (node (ref "C814") (pin "1") (pinfunction "1_1") (pintype "passive"))
      (node (ref "P801") (pin "100") (pinfunction "100_100") (pintype "passive"))
      (node (ref "P801") (pin "102") (pinfunction "102_102") (pintype "passive"))
      (node (ref "P801") (pin "104") (pinfunction "104_104") (pintype "passive"))
      (node (ref "P801") (pin "106") (pinfunction "106_106") (pintype "passive"))
      (node (ref "P801") (pin "108") (pinfunction "108_108") (pintype "passive"))
      (node (ref "P801") (pin "110") (pinfunction "110_110") (pintype "passive"))
      (node (ref "P801") (pin "112") (pinfunction "112_112") (pintype "passive"))
      (node (ref "P801") (pin "96") (pinfunction "96_96") (pintype "passive"))
      (node (ref "P801") (pin "98") (pinfunction "98_98") (pintype "passive"))
      (node (ref "TP814") (pin "1") (pinfunction "TP_1") (pintype "passive"))
    )
    (net (code "132") (name "nUSB_OTG_CHD") (class "Default")
      (node (ref "P801") (pin "31") (pinfunction "31_31") (pintype "passive"))
    )
    (net (code "133") (name "unconnected-(P801-Pad83)") (class "Default")
      (node (ref "P801") (pin "83") (pinfunction "83_83") (pintype "passive+no_connect"))
    )
    (net (code "134") (name "unconnected-(P801-Pad86)") (class "Default")
      (node (ref "P801") (pin "86") (pinfunction "86_86") (pintype "passive+no_connect"))
    )
    (net (code "135") (name "unconnected-(P801-Pad94)") (class "Default")
      (node (ref "P801") (pin "94") (pinfunction "94_94") (pintype "passive+no_connect"))
    )
    (net (code "136") (name "unconnected-(P801-Pad95)") (class "Default")
      (node (ref "P801") (pin "95") (pinfunction "95_95") (pintype "passive+no_connect"))
    )
  )
)
